# Aria-Fissa-pcb.net
KiCad netlist of a schematic drawn in EAGLE
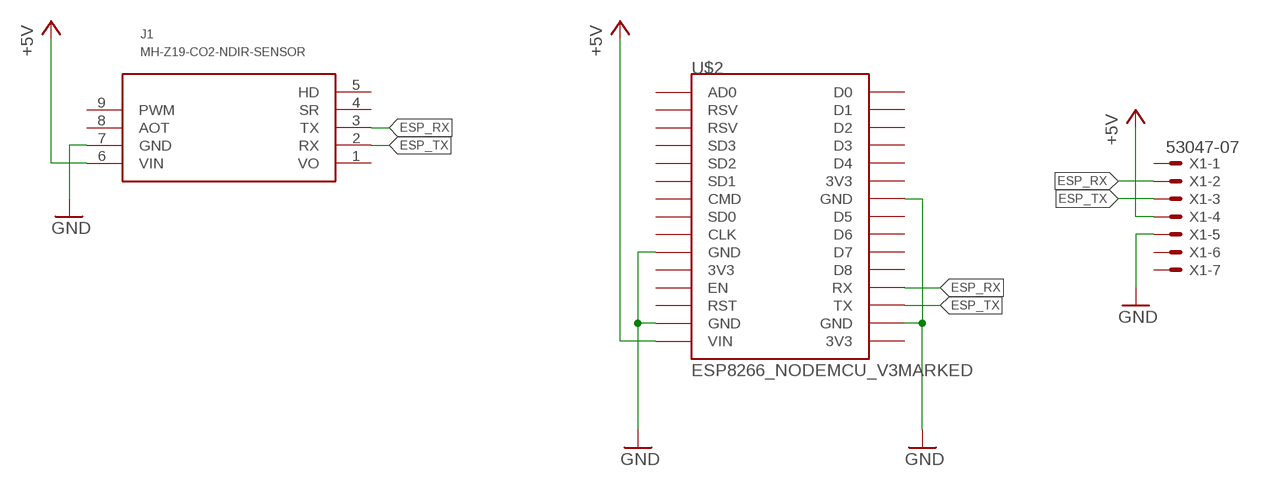
[diagram p0: schematic, sheet 1]

(export (version "E")
  (design (tool "Eeschema 10.0.6"))
  (components
    (comp (ref "J1")
      (value "MH-Z19-CO2-NDIR-SENSOR")
      (footprint "eagle-import:MH-Z19")
      (libsource (lib "eagle-import") (part "MH-Z19-CO2-NDIR-SENSOR"))
    )
    (comp (ref "U$2")
      (value "ESP8266_NODEMCU_V3MARKED")
      (footprint "eagle-import:ESP8266_NODEMCU_V3_SMALL")
      (libsource (lib "eagle-import") (part "ESP8266_NODEMCU_V3MARKED"))
    )
    (comp (ref "X1")
      (value "53047-07")
      (footprint "eagle-import:53047-07")
      (fields (field (name "MF") "MOLEX") (field (name "MPN") "53047-0710-C"))
      (libsource (lib "eagle-import") (part "53?-07047"))
    )
  )
  (nets
    (net (code "1") (name "+5V") (class "Default")
      (node (ref "J1") (pin "6") (pinfunction "VIN_6") (pintype "power_in"))
      (node (ref "U$2") (pin "VIN") (pinfunction "VIN_VIN") (pintype "bidirectional"))
      (node (ref "X1") (pin "4") (pinfunction "S_4") (pintype "passive"))
    )
    (net (code "2") (name "/VO") (class "Default")
      (node (ref "J1") (pin "1") (pinfunction "VO_1") (pintype "power_in"))
    )
    (net (code "3") (name "ESP_RX") (class "Default")
      (node (ref "J1") (pin "3") (pinfunction "TX_3") (pintype "output"))
      (node (ref "U$2") (pin "RX") (pinfunction "RX_RX") (pintype "bidirectional"))
      (node (ref "X1") (pin "2") (pinfunction "S_2") (pintype "passive"))
    )
    (net (code "4") (name "ESP_TX") (class "Default")
      (node (ref "J1") (pin "2") (pinfunction "RX_2") (pintype "input"))
      (node (ref "U$2") (pin "TX") (pinfunction "TX_TX") (pintype "bidirectional"))
      (node (ref "X1") (pin "3") (pinfunction "S_3") (pintype "passive"))
    )
    (net (code "5") (name "GND") (class "Default")
      (node (ref "J1") (pin "7") (pinfunction "GND_7") (pintype "power_in"))
      (node (ref "U$2") (pin "GND@0") (pinfunction "GND_GND@0") (pintype "bidirectional"))
      (node (ref "U$2") (pin "GND@1") (pinfunction "GND_GND@1") (pintype "bidirectional"))
      (node (ref "U$2") (pin "GND@2") (pinfunction "GND_GND@2") (pintype "bidirectional"))
      (node (ref "U$2") (pin "GND@3") (pinfunction "GND_GND@3") (pintype "bidirectional"))
      (node (ref "X1") (pin "5") (pinfunction "S_5") (pintype "passive"))
    )
    (net (code "6") (name "unconnected-(J1-AOT-Pad8)") (class "Default")
      (node (ref "J1") (pin "8") (pinfunction "AOT_8") (pintype "no_connect"))
    )
    (net (code "7") (name "unconnected-(J1-HD-Pad5)") (class "Default")
      (node (ref "J1") (pin "5") (pinfunction "HD_5") (pintype "input"))
    )
    (net (code "8") (name "unconnected-(J1-PWM-Pad9)") (class "Default")
      (node (ref "J1") (pin "9") (pinfunction "PWM_9") (pintype "output"))
    )
    (net (code "9") (name "unconnected-(J1-SR-Pad4)") (class "Default")
      (node (ref "J1") (pin "4") (pinfunction "SR_4") (pintype "no_connect"))
    )
    (net (code "10") (name "unconnected-(U$2-3V3-Pad3V3@0)") (class "Default")
      (node (ref "U$2") (pin "3V3@0") (pinfunction "3V3_3V3@0") (pintype "bidirectional"))
    )
    (net (code "11") (name "unconnected-(U$2-3V3-Pad3V3@1)") (class "Default")
      (node (ref "U$2") (pin "3V3@1") (pinfunction "3V3_3V3@1") (pintype "bidirectional"))
    )
    (net (code "12") (name "unconnected-(U$2-3V3-Pad3V3@2)") (class "Default")
      (node (ref "U$2") (pin "3V3@2") (pinfunction "3V3_3V3@2") (pintype "bidirectional"))
    )
    (net (code "13") (name "unconnected-(U$2-PadAD0)") (class "Default")
      (node (ref "U$2") (pin "AD0") (pinfunction "AD0_AD0") (pintype "bidirectional"))
    )
    (net (code "14") (name "unconnected-(U$2-PadCLK)") (class "Default")
      (node (ref "U$2") (pin "CLK") (pinfunction "CLK_CLK") (pintype "bidirectional"))
    )
    (net (code "15") (name "unconnected-(U$2-PadCMD)") (class "Default")
      (node (ref "U$2") (pin "CMD") (pinfunction "CMD_CMD") (pintype "bidirectional"))
    )
    (net (code "16") (name "unconnected-(U$2-PadD0)") (class "Default")
      (node (ref "U$2") (pin "D0") (pinfunction "D0_D0") (pintype "bidirectional"))
    )
    (net (code "17") (name "unconnected-(U$2-PadD1)") (class "Default")
      (node (ref "U$2") (pin "D1") (pinfunction "D1_D1") (pintype "bidirectional"))
    )
    (net (code "18") (name "unconnected-(U$2-PadD2)") (class "Default")
      (node (ref "U$2") (pin "D2") (pinfunction "D2_D2") (pintype "bidirectional"))
    )
    (net (code "19") (name "unconnected-(U$2-PadD3)") (class "Default")
      (node (ref "U$2") (pin "D3") (pinfunction "D3_D3") (pintype "bidirectional"))
    )
    (net (code "20") (name "unconnected-(U$2-PadD4)") (class "Default")
      (node (ref "U$2") (pin "D4") (pinfunction "D4_D4") (pintype "bidirectional"))
    )
    (net (code "21") (name "unconnected-(U$2-PadD5)") (class "Default")
      (node (ref "U$2") (pin "D5") (pinfunction "D5_D5") (pintype "bidirectional"))
    )
    (net (code "22") (name "unconnected-(U$2-PadD6)") (class "Default")
      (node (ref "U$2") (pin "D6") (pinfunction "D6_D6") (pintype "bidirectional"))
    )
    (net (code "23") (name "unconnected-(U$2-PadD7)") (class "Default")
      (node (ref "U$2") (pin "D7") (pinfunction "D7_D7") (pintype "bidirectional"))
    )
    (net (code "24") (name "unconnected-(U$2-PadD8)") (class "Default")
      (node (ref "U$2") (pin "D8") (pinfunction "D8_D8") (pintype "bidirectional"))
    )
    (net (code "25") (name "unconnected-(U$2-PadEN)") (class "Default")
      (node (ref "U$2") (pin "EN") (pinfunction "EN_EN") (pintype "bidirectional"))
    )
    (net (code "26") (name "unconnected-(U$2-PadRST)") (class "Default")
      (node (ref "U$2") (pin "RST") (pinfunction "RST_RST") (pintype "bidirectional"))
    )
    (net (code "27") (name "unconnected-(U$2-PadSD0)") (class "Default")
      (node (ref "U$2") (pin "SD0") (pinfunction "SD0_SD0") (pintype "bidirectional"))
    )
    (net (code "28") (name "unconnected-(U$2-PadSD1)") (class "Default")
      (node (ref "U$2") (pin "SD1") (pinfunction "SD1_SD1") (pintype "bidirectional"))
    )
    (net (code "29") (name "unconnected-(U$2-PadSD2)") (class "Default")
      (node (ref "U$2") (pin "SD2") (pinfunction "SD2_SD2") (pintype "bidirectional"))
    )
    (net (code "30") (name "unconnected-(U$2-PadSD3)") (class "Default")
      (node (ref "U$2") (pin "SD3") (pinfunction "SD3_SD3") (pintype "bidirectional"))
    )
    (net (code "31") (name "unconnected-(U$2-RSV-PadRSV@0)") (class "Default")
      (node (ref "U$2") (pin "RSV@0") (pinfunction "RSV_RSV@0") (pintype "bidirectional"))
    )
    (net (code "32") (name "unconnected-(U$2-RSV-PadRSV@1)") (class "Default")
      (node (ref "U$2") (pin "RSV@1") (pinfunction "RSV_RSV@1") (pintype "bidirectional"))
    )
    (net (code "33") (name "unconnected-(X1A-S-Pad1)") (class "Default")
      (node (ref "X1") (pin "1") (pinfunction "S_1") (pintype "passive"))
    )
    (net (code "34") (name "unconnected-(X1F-S-Pad6)") (class "Default")
      (node (ref "X1") (pin "6") (pinfunction "S_6") (pintype "passive"))
    )
    (net (code "35") (name "unconnected-(X1G-S-Pad7)") (class "Default")
      (node (ref "X1") (pin "7") (pinfunction "S_7") (pintype "passive"))
    )
  )
)
